# oximeter.net
KiCad netlist of a schematic drawn in EAGLE
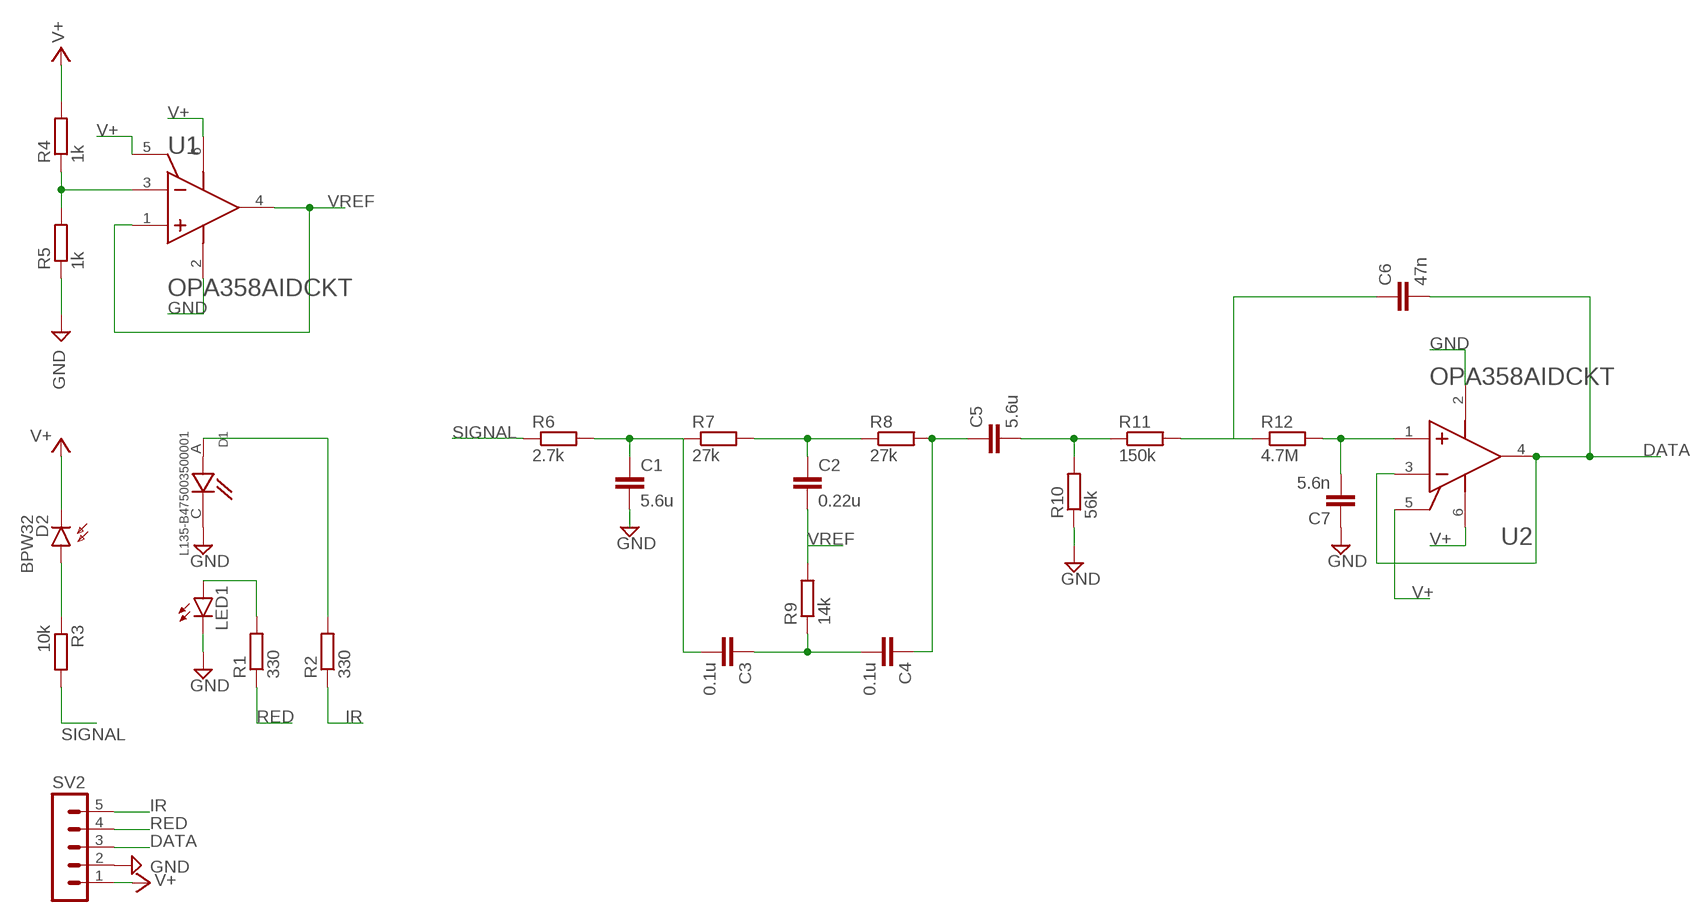
[diagram p0: schematic, sheet 1]

(export (version "E")
  (design (tool "Eeschema 10.0.6"))
  (components
    (comp (ref "C1")
      (value "5.6u")
      (footprint "eagle-import:C0603")
      (libsource (lib "eagle-import") (part "C-EUC0603"))
    )
    (comp (ref "C2")
      (value "0.22u")
      (footprint "eagle-import:C0603")
      (libsource (lib "eagle-import") (part "C-EUC0603"))
    )
    (comp (ref "C3")
      (value "0.1u")
      (footprint "eagle-import:C0603")
      (libsource (lib "eagle-import") (part "C-EUC0603"))
    )
    (comp (ref "C4")
      (value "0.1u")
      (footprint "eagle-import:C0603")
      (libsource (lib "eagle-import") (part "C-EUC0603"))
    )
    (comp (ref "C5")
      (value "5.6u")
      (footprint "eagle-import:C0603")
      (libsource (lib "eagle-import") (part "C-EUC0603"))
    )
    (comp (ref "C6")
      (value "47n")
      (footprint "eagle-import:C0603")
      (libsource (lib "eagle-import") (part "C-EUC0603"))
    )
    (comp (ref "C7")
      (value "5.6n")
      (footprint "eagle-import:C0603")
      (libsource (lib "eagle-import") (part "C-EUC0603"))
    )
    (comp (ref "D1")
      (value "L135-B475003500001")
      (footprint "eagle-import:LED_L135-B475003500001")
      (fields (field (name "MF") "Lumileds"))
      (libsource (lib "eagle-import") (part "L135-B475003500001"))
    )
    (comp (ref "D2")
      (value "BPW32")
      (footprint "eagle-import:BPW32")
      (libsource (lib "eagle-import") (part "BPW32"))
    )
    (comp (ref "LED1")
      (value "LEDCHIP-LED0603")
      (footprint "eagle-import:CHIP-LED0603")
      (libsource (lib "eagle-import") (part "LEDCHIP-LED0603"))
    )
    (comp (ref "R1")
      (value "330")
      (footprint "eagle-import:R0603")
      (libsource (lib "eagle-import") (part "R-EU_R0603"))
    )
    (comp (ref "R2")
      (value "330")
      (footprint "eagle-import:R0603")
      (libsource (lib "eagle-import") (part "R-EU_R0603"))
    )
    (comp (ref "R3")
      (value "10k")
      (footprint "eagle-import:R0603")
      (libsource (lib "eagle-import") (part "R-EU_R0603"))
    )
    (comp (ref "R4")
      (value "1k")
      (footprint "eagle-import:R0603")
      (libsource (lib "eagle-import") (part "R-EU_R0603"))
    )
    (comp (ref "R5")
      (value "1k")
      (footprint "eagle-import:R0603")
      (libsource (lib "eagle-import") (part "R-EU_R0603"))
    )
    (comp (ref "R6")
      (value "2.7k")
      (footprint "eagle-import:R0603")
      (libsource (lib "eagle-import") (part "R-EU_R0603"))
    )
    (comp (ref "R7")
      (value "27k")
      (footprint "eagle-import:R0603")
      (libsource (lib "eagle-import") (part "R-EU_R0603"))
    )
    (comp (ref "R8")
      (value "27k")
      (footprint "eagle-import:R0603")
      (libsource (lib "eagle-import") (part "R-EU_R0603"))
    )
    (comp (ref "R9")
      (value "14k")
      (footprint "eagle-import:R0603")
      (libsource (lib "eagle-import") (part "R-EU_R0603"))
    )
    (comp (ref "R10")
      (value "56k")
      (footprint "eagle-import:R0603")
      (libsource (lib "eagle-import") (part "R-EU_R0603"))
    )
    (comp (ref "R11")
      (value "150k")
      (footprint "eagle-import:R0603")
      (libsource (lib "eagle-import") (part "R-EU_R0603"))
    )
    (comp (ref "R12")
      (value "4.7M")
      (footprint "eagle-import:R0603")
      (libsource (lib "eagle-import") (part "R-EU_R0603"))
    )
    (comp (ref "SV2")
      (value "MA05-1")
      (footprint "eagle-import:MA05-1")
      (libsource (lib "eagle-import") (part "MA05-1"))
    )
    (comp (ref "U1")
      (value "TEXAS_INSTRUMENTS_OPA358AIDCKTTEXAS_INSTRUMENTS_OPA358AIDCKT_0_0")
      (footprint "eagle-import:TEXAS_INSTRUMENTS_OPA358AIDCKT_0")
      (fields (field (name "MF") "Texas Instruments") (field (name "MPN") "OPA358AIDCKT"))
      (libsource (lib "eagle-import") (part "TEXAS_INSTRUMENTS_OPA358AIDCKTTEXAS_INSTRUMENTS_OPA358AIDCKT_0_0"))
    )
    (comp (ref "U2")
      (value "TEXAS_INSTRUMENTS_OPA358AIDCKTTEXAS_INSTRUMENTS_OPA358AIDCKT_0_0")
      (footprint "eagle-import:TEXAS_INSTRUMENTS_OPA358AIDCKT_0")
      (fields (field (name "MF") "Texas Instruments") (field (name "MPN") "OPA358AIDCKT"))
      (libsource (lib "eagle-import") (part "TEXAS_INSTRUMENTS_OPA358AIDCKTTEXAS_INSTRUMENTS_OPA358AIDCKT_0_0"))
    )
  )
  (nets
    (net (code "1") (name "/DATA") (class "Default")
      (node (ref "C6") (pin "2") (pinfunction "2_2") (pintype "passive"))
      (node (ref "SV2") (pin "3") (pinfunction "3_3") (pintype "passive"))
      (node (ref "U2") (pin "3") (pinfunction "IN-_3") (pintype "input"))
      (node (ref "U2") (pin "4") (pinfunction "OUT_4") (pintype "tri_state"))
    )
    (net (code "2") (name "/IR") (class "Default")
      (node (ref "R2") (pin "1") (pinfunction "1_1") (pintype "passive"))
      (node (ref "SV2") (pin "5") (pinfunction "5_5") (pintype "passive"))
    )
    (net (code "3") (name "/RED") (class "Default")
      (node (ref "R1") (pin "1") (pinfunction "1_1") (pintype "passive"))
      (node (ref "SV2") (pin "4") (pinfunction "4_4") (pintype "passive"))
    )
    (net (code "4") (name "/SIGNAL") (class "Default")
      (node (ref "R3") (pin "2") (pinfunction "2_2") (pintype "passive"))
      (node (ref "R6") (pin "1") (pinfunction "1_1") (pintype "passive"))
    )
    (net (code "5") (name "/VREF") (class "Default")
      (node (ref "C2") (pin "2") (pinfunction "2_2") (pintype "passive"))
      (node (ref "R9") (pin "2") (pinfunction "2_2") (pintype "passive"))
      (node (ref "U1") (pin "1") (pinfunction "IN+_1") (pintype "input"))
      (node (ref "U1") (pin "4") (pinfunction "OUT_4") (pintype "tri_state"))
    )
    (net (code "6") (name "GND") (class "Default")
      (node (ref "C1") (pin "2") (pinfunction "2_2") (pintype "passive"))
      (node (ref "C7") (pin "1") (pinfunction "1_1") (pintype "passive"))
      (node (ref "D1") (pin "C") (pinfunction "C_C") (pintype "passive"))
      (node (ref "LED1") (pin "C") (pinfunction "C_C") (pintype "passive"))
      (node (ref "R10") (pin "1") (pinfunction "1_1") (pintype "passive"))
      (node (ref "R5") (pin "1") (pinfunction "1_1") (pintype "passive"))
      (node (ref "SV2") (pin "2") (pinfunction "2_2") (pintype "passive"))
      (node (ref "U1") (pin "2") (pinfunction "GND_2") (pintype "power_in"))
      (node (ref "U2") (pin "2") (pinfunction "GND_2") (pintype "power_in"))
    )
    (net (code "7") (name "Net-(C1-Pad1)") (class "Default")
      (node (ref "C1") (pin "1") (pinfunction "1_1") (pintype "passive"))
      (node (ref "C3") (pin "2") (pinfunction "2_2") (pintype "passive"))
      (node (ref "R6") (pin "2") (pinfunction "2_2") (pintype "passive"))
      (node (ref "R7") (pin "1") (pinfunction "1_1") (pintype "passive"))
    )
    (net (code "8") (name "Net-(C2-Pad1)") (class "Default")
      (node (ref "C2") (pin "1") (pinfunction "1_1") (pintype "passive"))
      (node (ref "R7") (pin "2") (pinfunction "2_2") (pintype "passive"))
      (node (ref "R8") (pin "1") (pinfunction "1_1") (pintype "passive"))
    )
    (net (code "9") (name "Net-(C3-Pad1)") (class "Default")
      (node (ref "C3") (pin "1") (pinfunction "1_1") (pintype "passive"))
      (node (ref "C4") (pin "2") (pinfunction "2_2") (pintype "passive"))
      (node (ref "R9") (pin "1") (pinfunction "1_1") (pintype "passive"))
    )
    (net (code "10") (name "Net-(C4-Pad1)") (class "Default")
      (node (ref "C4") (pin "1") (pinfunction "1_1") (pintype "passive"))
      (node (ref "C5") (pin "1") (pinfunction "1_1") (pintype "passive"))
      (node (ref "R8") (pin "2") (pinfunction "2_2") (pintype "passive"))
    )
    (net (code "11") (name "Net-(C5-Pad2)") (class "Default")
      (node (ref "C5") (pin "2") (pinfunction "2_2") (pintype "passive"))
      (node (ref "R10") (pin "2") (pinfunction "2_2") (pintype "passive"))
      (node (ref "R11") (pin "1") (pinfunction "1_1") (pintype "passive"))
    )
    (net (code "12") (name "Net-(C6-Pad1)") (class "Default")
      (node (ref "C6") (pin "1") (pinfunction "1_1") (pintype "passive"))
      (node (ref "R11") (pin "2") (pinfunction "2_2") (pintype "passive"))
      (node (ref "R12") (pin "1") (pinfunction "1_1") (pintype "passive"))
    )
    (net (code "13") (name "Net-(D1-PadA)") (class "Default")
      (node (ref "D1") (pin "A") (pinfunction "A_A") (pintype "passive"))
      (node (ref "R2") (pin "2") (pinfunction "2_2") (pintype "passive"))
    )
    (net (code "14") (name "Net-(D2-PadA)") (class "Default")
      (node (ref "D2") (pin "A") (pinfunction "A_A") (pintype "passive"))
      (node (ref "R3") (pin "1") (pinfunction "1_1") (pintype "passive"))
    )
    (net (code "15") (name "Net-(LED1-PadA)") (class "Default")
      (node (ref "LED1") (pin "A") (pinfunction "A_A") (pintype "passive"))
      (node (ref "R1") (pin "2") (pinfunction "2_2") (pintype "passive"))
    )
    (net (code "16") (name "Net-(U1-IN-)") (class "Default")
      (node (ref "R4") (pin "1") (pinfunction "1_1") (pintype "passive"))
      (node (ref "R5") (pin "2") (pinfunction "2_2") (pintype "passive"))
      (node (ref "U1") (pin "3") (pinfunction "IN-_3") (pintype "input"))
    )
    (net (code "17") (name "Net-(U2-IN+)") (class "Default")
      (node (ref "C7") (pin "2") (pinfunction "2_2") (pintype "passive"))
      (node (ref "R12") (pin "2") (pinfunction "2_2") (pintype "passive"))
      (node (ref "U2") (pin "1") (pinfunction "IN+_1") (pintype "input"))
    )
    (net (code "18") (name "V+") (class "Default")
      (node (ref "D2") (pin "K") (pinfunction "C_K") (pintype "passive"))
      (node (ref "R4") (pin "2") (pinfunction "2_2") (pintype "passive"))
      (node (ref "SV2") (pin "1") (pinfunction "1_1") (pintype "passive"))
      (node (ref "U1") (pin "5") (pinfunction "ENABLE_5") (pintype "input"))
      (node (ref "U1") (pin "6") (pinfunction "V+_6") (pintype "power_in"))
      (node (ref "U2") (pin "5") (pinfunction "ENABLE_5") (pintype "input"))
      (node (ref "U2") (pin "6") (pinfunction "V+_6") (pintype "power_in"))
    )
  )
)
